# HOTAS_TOP_v4_v10.net
KiCad netlist of a schematic drawn in EAGLE
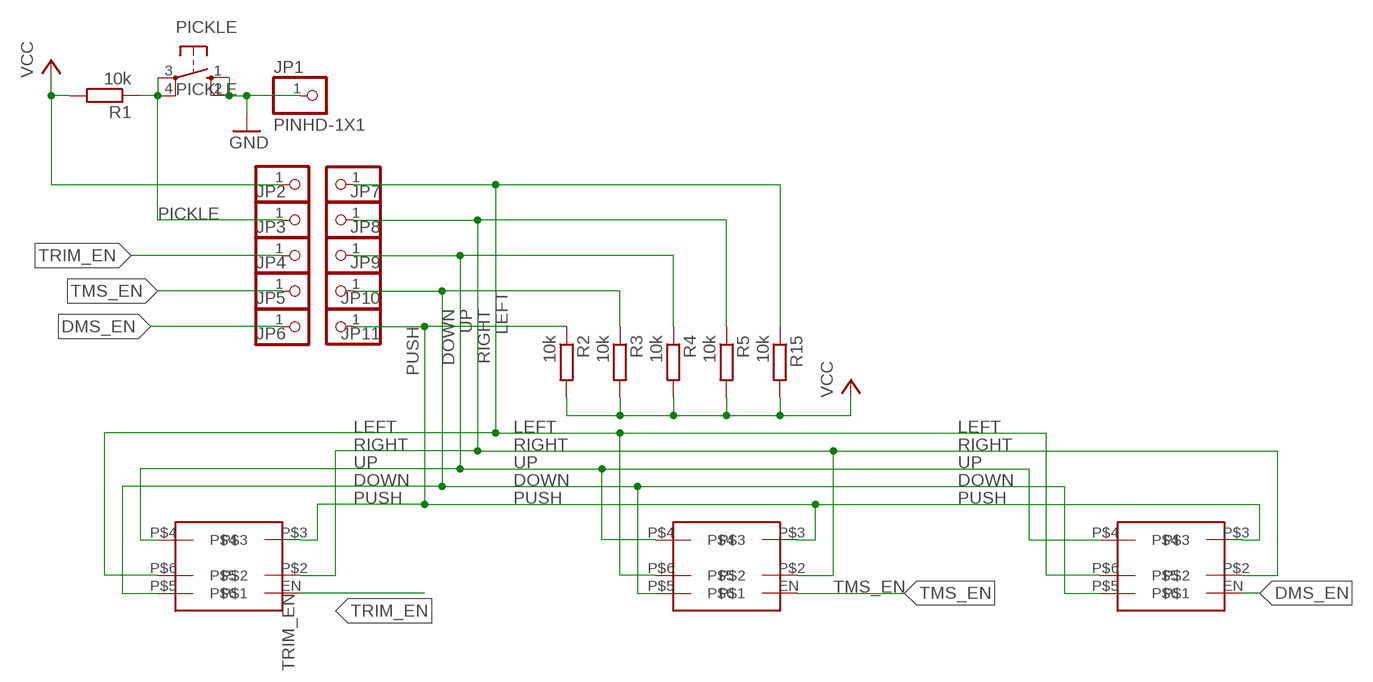
[diagram p0: schematic, sheet 1]

(export (version "E")
  (design (tool "Eeschema 10.0.6"))
  (components
    (comp (ref "JP1")
      (value "PINHD-1X1")
      (footprint "eagle-import:1X01")
      (fields (field (name "MANUFACTURER") "Generic"))
      (libsource (lib "eagle-import") (part "PINHD-1X1"))
    )
    (comp (ref "JP2")
      (value "PINHD-1X1")
      (footprint "eagle-import:1X01")
      (fields (field (name "MANUFACTURER") "Generic"))
      (libsource (lib "eagle-import") (part "PINHD-1X1"))
    )
    (comp (ref "JP3")
      (value "PINHD-1X1")
      (footprint "eagle-import:1X01")
      (fields (field (name "MANUFACTURER") "Generic"))
      (libsource (lib "eagle-import") (part "PINHD-1X1"))
    )
    (comp (ref "JP4")
      (value "PINHD-1X1")
      (footprint "eagle-import:1X01")
      (fields (field (name "MANUFACTURER") "Generic"))
      (libsource (lib "eagle-import") (part "PINHD-1X1"))
    )
    (comp (ref "JP5")
      (value "PINHD-1X1")
      (footprint "eagle-import:1X01")
      (fields (field (name "MANUFACTURER") "Generic"))
      (libsource (lib "eagle-import") (part "PINHD-1X1"))
    )
    (comp (ref "JP6")
      (value "PINHD-1X1")
      (footprint "eagle-import:1X01")
      (fields (field (name "MANUFACTURER") "Generic"))
      (libsource (lib "eagle-import") (part "PINHD-1X1"))
    )
    (comp (ref "JP7")
      (value "PINHD-1X1")
      (footprint "eagle-import:1X01")
      (fields (field (name "MANUFACTURER") "Generic"))
      (libsource (lib "eagle-import") (part "PINHD-1X1"))
    )
    (comp (ref "JP8")
      (value "PINHD-1X1")
      (footprint "eagle-import:1X01")
      (fields (field (name "MANUFACTURER") "Generic"))
      (libsource (lib "eagle-import") (part "PINHD-1X1"))
    )
    (comp (ref "JP9")
      (value "PINHD-1X1")
      (footprint "eagle-import:1X01")
      (fields (field (name "MANUFACTURER") "Generic"))
      (libsource (lib "eagle-import") (part "PINHD-1X1"))
    )
    (comp (ref "JP10")
      (value "PINHD-1X1")
      (footprint "eagle-import:1X01")
      (fields (field (name "MANUFACTURER") "Generic"))
      (libsource (lib "eagle-import") (part "PINHD-1X1"))
    )
    (comp (ref "JP11")
      (value "PINHD-1X1")
      (footprint "eagle-import:1X01")
      (fields (field (name "MANUFACTURER") "Generic"))
      (libsource (lib "eagle-import") (part "PINHD-1X1"))
    )
    (comp (ref "PICKLE")
      (value "10-XX")
      (footprint "eagle-import:B3F-10XX")
      (fields (field (name "MPN") "B3F-1000"))
      (libsource (lib "eagle-import") (part "10-XX"))
    )
    (comp (ref "R1")
      (value "10k")
      (footprint "eagle-import:RESC3216X70")
      (libsource (lib "eagle-import") (part "RCHIP-1206(3216-METRIC)_"))
    )
    (comp (ref "R2")
      (value "10k")
      (footprint "eagle-import:RESC3216X70")
      (libsource (lib "eagle-import") (part "RCHIP-1206(3216-METRIC)_"))
    )
    (comp (ref "R3")
      (value "10k")
      (footprint "eagle-import:RESC3216X70")
      (libsource (lib "eagle-import") (part "RCHIP-1206(3216-METRIC)_"))
    )
    (comp (ref "R4")
      (value "10k")
      (footprint "eagle-import:RESC3216X70")
      (libsource (lib "eagle-import") (part "RCHIP-1206(3216-METRIC)_"))
    )
    (comp (ref "R5")
      (value "10k")
      (footprint "eagle-import:RESC3216X70")
      (libsource (lib "eagle-import") (part "RCHIP-1206(3216-METRIC)_"))
    )
    (comp (ref "R15")
      (value "10k")
      (footprint "eagle-import:RESC3216X70")
      (libsource (lib "eagle-import") (part "RCHIP-1206(3216-METRIC)_"))
    )
    (comp (ref "U$1")
      (value "FIVEWAYHATSSMD")
      (footprint "eagle-import:FIVEWAYHATSSMD")
      (libsource (lib "eagle-import") (part "FIVEWAYHATSSMD"))
    )
    (comp (ref "U$2")
      (value "FIVEWAYHATSSMD")
      (footprint "eagle-import:FIVEWAYHATSSMD")
      (libsource (lib "eagle-import") (part "FIVEWAYHATSSMD"))
    )
    (comp (ref "U$3")
      (value "FIVEWAYHATSSMD")
      (footprint "eagle-import:FIVEWAYHATSSMD")
      (libsource (lib "eagle-import") (part "FIVEWAYHATSSMD"))
    )
  )
  (nets
    (net (code "1") (name "/DOWN") (class "Default")
      (node (ref "JP10") (pin "1") (pinfunction "1_1") (pintype "passive"))
      (node (ref "R3") (pin "1") (pinfunction "1_1") (pintype "passive"))
      (node (ref "U$1") (pin "P$5") (pinfunction "P$6_P$5") (pintype "bidirectional"))
      (node (ref "U$2") (pin "P$5") (pinfunction "P$6_P$5") (pintype "bidirectional"))
      (node (ref "U$3") (pin "P$5") (pinfunction "P$6_P$5") (pintype "bidirectional"))
    )
    (net (code "2") (name "/LEFT") (class "Default")
      (node (ref "JP7") (pin "1") (pinfunction "1_1") (pintype "passive"))
      (node (ref "R15") (pin "1") (pinfunction "1_1") (pintype "passive"))
      (node (ref "U$1") (pin "P$6") (pinfunction "P$5_P$6") (pintype "bidirectional"))
      (node (ref "U$2") (pin "P$6") (pinfunction "P$5_P$6") (pintype "bidirectional"))
      (node (ref "U$3") (pin "P$6") (pinfunction "P$5_P$6") (pintype "bidirectional"))
    )
    (net (code "3") (name "/PICKLE") (class "Default")
      (node (ref "JP3") (pin "1") (pinfunction "1_1") (pintype "passive"))
      (node (ref "PICKLE") (pin "3") (pinfunction "P_3") (pintype "passive"))
      (node (ref "PICKLE") (pin "4") (pinfunction "P1_4") (pintype "passive"))
      (node (ref "R1") (pin "1") (pinfunction "1_1") (pintype "passive"))
    )
    (net (code "4") (name "/PUSH") (class "Default")
      (node (ref "JP11") (pin "1") (pinfunction "1_1") (pintype "passive"))
      (node (ref "R2") (pin "1") (pinfunction "1_1") (pintype "passive"))
      (node (ref "U$1") (pin "P$3") (pinfunction "P$3_P$3") (pintype "bidirectional"))
      (node (ref "U$2") (pin "P$3") (pinfunction "P$3_P$3") (pintype "bidirectional"))
      (node (ref "U$3") (pin "P$3") (pinfunction "P$3_P$3") (pintype "bidirectional"))
    )
    (net (code "5") (name "/RIGHT") (class "Default")
      (node (ref "JP8") (pin "1") (pinfunction "1_1") (pintype "passive"))
      (node (ref "R5") (pin "1") (pinfunction "1_1") (pintype "passive"))
      (node (ref "U$1") (pin "P$2") (pinfunction "P$2_P$2") (pintype "bidirectional"))
      (node (ref "U$2") (pin "P$2") (pinfunction "P$2_P$2") (pintype "bidirectional"))
      (node (ref "U$3") (pin "P$2") (pinfunction "P$2_P$2") (pintype "bidirectional"))
    )
    (net (code "6") (name "/UP") (class "Default")
      (node (ref "JP9") (pin "1") (pinfunction "1_1") (pintype "passive"))
      (node (ref "R4") (pin "1") (pinfunction "1_1") (pintype "passive"))
      (node (ref "U$1") (pin "P$4") (pinfunction "P$4_P$4") (pintype "bidirectional"))
      (node (ref "U$2") (pin "P$4") (pinfunction "P$4_P$4") (pintype "bidirectional"))
      (node (ref "U$3") (pin "P$4") (pinfunction "P$4_P$4") (pintype "bidirectional"))
    )
    (net (code "7") (name "DMS_EN") (class "Default")
      (node (ref "JP6") (pin "1") (pinfunction "1_1") (pintype "passive"))
      (node (ref "U$3") (pin "EN") (pinfunction "P$1_EN") (pintype "bidirectional"))
    )
    (net (code "8") (name "GND") (class "Default")
      (node (ref "JP1") (pin "1") (pinfunction "1_1") (pintype "passive"))
      (node (ref "PICKLE") (pin "1") (pinfunction "S_1") (pintype "passive"))
      (node (ref "PICKLE") (pin "2") (pinfunction "S1_2") (pintype "passive"))
    )
    (net (code "9") (name "TMS_EN") (class "Default")
      (node (ref "JP5") (pin "1") (pinfunction "1_1") (pintype "passive"))
      (node (ref "U$2") (pin "EN") (pinfunction "P$1_EN") (pintype "bidirectional"))
    )
    (net (code "10") (name "TRIM_EN") (class "Default")
      (node (ref "JP4") (pin "1") (pinfunction "1_1") (pintype "passive"))
      (node (ref "U$1") (pin "EN") (pinfunction "P$1_EN") (pintype "bidirectional"))
    )
    (net (code "11") (name "VCC") (class "Default")
      (node (ref "JP2") (pin "1") (pinfunction "1_1") (pintype "passive"))
      (node (ref "R1") (pin "2") (pinfunction "2_2") (pintype "passive"))
      (node (ref "R15") (pin "2") (pinfunction "2_2") (pintype "passive"))
      (node (ref "R2") (pin "2") (pinfunction "2_2") (pintype "passive"))
      (node (ref "R3") (pin "2") (pinfunction "2_2") (pintype "passive"))
      (node (ref "R4") (pin "2") (pinfunction "2_2") (pintype "passive"))
      (node (ref "R5") (pin "2") (pinfunction "2_2") (pintype "passive"))
    )
  )
)
